# Power.net
KiCad netlist of a schematic drawn in Altium Designer
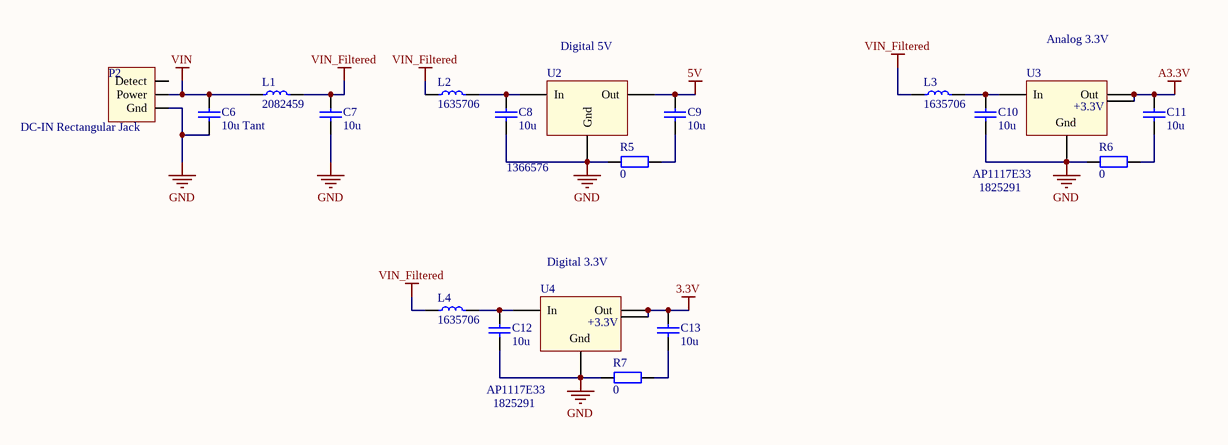
[diagram p0: Power.SchDoc]

(export (version "E")
  (design (tool "Eeschema 10.0.6"))
  (components
    (comp (ref "C6") (value "10u Tant") (footprint "CAPC3216M") (libsource (lib "Passives") (part "C")))
    (comp (ref "C7") (value "10u") (footprint "CAPC2012M") (libsource (lib "Passives") (part "C")))
    (comp (ref "C8") (value "10u") (footprint "CAPC2012M") (libsource (lib "Passives") (part "C")))
    (comp (ref "C9") (value "10u") (footprint "CAPC2012M") (libsource (lib "Passives") (part "C")))
    (comp (ref "C10") (value "10u") (footprint "CAPC2012M") (libsource (lib "Passives") (part "C")))
    (comp (ref "C11") (value "10u") (footprint "CAPC2012M") (libsource (lib "Passives") (part "C")))
    (comp (ref "C12") (value "10u") (footprint "CAPC2012M") (libsource (lib "Passives") (part "C")))
    (comp (ref "C13") (value "10u") (footprint "CAPC2012M") (libsource (lib "Passives") (part "C")))
    (comp (ref "L1")
      (value "Wurth_742792901")
      (footprint "WE_742792901")
      (description "Ferrite bead, 1.1k Ohm, 10A, (Wurth 742792901)")
      (fields (field (name "SUPPLIER PART NUMBER 1") "2082459"))
      (libsource (lib "Passives") (part "Wurth_742792901"))
    )
    (comp (ref "L2")
      (value "FerriteBead_600R")
      (footprint "INDC1608M")
      (description "Ferrite bead,  600 Ohm, 1A")
      (fields (field (name "SUPPLIER PART NUMBER 1") "1635706"))
      (libsource (lib "Passives") (part "FerriteBead_600R"))
    )
    (comp (ref "L3")
      (value "FerriteBead_600R")
      (footprint "INDC1608M")
      (description "Ferrite bead,  600 Ohm, 1A")
      (fields (field (name "SUPPLIER PART NUMBER 1") "1635706"))
      (libsource (lib "Passives") (part "FerriteBead_600R"))
    )
    (comp (ref "L4")
      (value "FerriteBead_600R")
      (footprint "INDC1608M")
      (description "Ferrite bead,  600 Ohm, 1A")
      (fields (field (name "SUPPLIER PART NUMBER 1") "1635706"))
      (libsource (lib "Passives") (part "FerriteBead_600R"))
    )
    (comp (ref "P2")
      (value "DC-IN Rectangular Jack")
      (footprint "DC-IN-RECT-JACK-PCB")
      (libsource (lib "Connectors") (part "DC-IN Rectangular Jack"))
    )
    (comp (ref "R5") (value "0") (footprint "RESC1608M") (libsource (lib "Passives") (part "R")))
    (comp (ref "R6") (value "0") (footprint "RESC1608M") (libsource (lib "Passives") (part "R")))
    (comp (ref "R7") (value "0") (footprint "RESC1608M") (libsource (lib "Passives") (part "R")))
    (comp (ref "U2")
      (value "L7805CD2T-TR")
      (footprint "D2PAK_M")
      (description "5V 500mA linear regulator, D2PAK-3")
      (fields (field (name "SUPPLIER PART NUMBER 1") "1366576"))
      (libsource (lib "Linear") (part "L7805CD2T-TR"))
    )
    (comp (ref "U3")
      (value "AP1117E33")
      (footprint "SOT223-4M")
      (description "3.3V 1A LDO linear regulator")
      (fields (field (name "SUPPLIER PART NUMBER 1") "1825291"))
      (libsource (lib "Linear") (part "AP1117E33"))
    )
    (comp (ref "U4")
      (value "AP1117E33")
      (footprint "SOT223-4M")
      (description "3.3V 1A LDO linear regulator")
      (fields (field (name "SUPPLIER PART NUMBER 1") "1825291"))
      (libsource (lib "Linear") (part "AP1117E33"))
    )
  )
  (nets
    (net (code "1") (name "3.3V") (class "Default")
      (node (ref "C13") (pin "2") (pinfunction "2_2") (pintype "passive"))
      (node (ref "U4") (pin "Out") (pinfunction "Out_Out") (pintype "power_in"))
      (node (ref "U4") (pin "Out2") (pinfunction "Out2_Out2") (pintype "power_in"))
    )
    (net (code "2") (name "5V") (class "Default")
      (node (ref "C9") (pin "2") (pinfunction "2_2") (pintype "passive"))
      (node (ref "U2") (pin "Out") (pinfunction "Out_Out") (pintype "power_in"))
    )
    (net (code "3") (name "A3.3V") (class "Default")
      (node (ref "C11") (pin "2") (pinfunction "2_2") (pintype "passive"))
      (node (ref "U3") (pin "Out") (pinfunction "Out_Out") (pintype "power_in"))
      (node (ref "U3") (pin "Out2") (pinfunction "Out2_Out2") (pintype "power_in"))
    )
    (net (code "4") (name "GND") (class "Default")
      (node (ref "C10") (pin "1") (pinfunction "1_1") (pintype "passive"))
      (node (ref "C12") (pin "1") (pinfunction "1_1") (pintype "passive"))
      (node (ref "C6") (pin "2") (pinfunction "2_2") (pintype "passive"))
      (node (ref "C7") (pin "1") (pinfunction "1_1") (pintype "passive"))
      (node (ref "C8") (pin "1") (pinfunction "1_1") (pintype "passive"))
      (node (ref "P2") (pin "Gnd") (pinfunction "Gnd_Gnd") (pintype "passive"))
      (node (ref "R5") (pin "2") (pinfunction "2_2") (pintype "passive"))
      (node (ref "R6") (pin "2") (pinfunction "2_2") (pintype "passive"))
      (node (ref "R7") (pin "2") (pinfunction "2_2") (pintype "passive"))
      (node (ref "U2") (pin "Gnd") (pinfunction "Gnd_Gnd") (pintype "passive"))
      (node (ref "U3") (pin "Gnd") (pinfunction "Gnd_Gnd") (pintype "passive"))
      (node (ref "U4") (pin "Gnd") (pinfunction "Gnd_Gnd") (pintype "passive"))
    )
    (net (code "5") (name "Net-(C8-Pad2)") (class "Default")
      (node (ref "C8") (pin "2") (pinfunction "2_2") (pintype "passive"))
      (node (ref "L2") (pin "2") (pinfunction "2_2") (pintype "passive"))
      (node (ref "U2") (pin "In") (pinfunction "In_In") (pintype "power_in"))
    )
    (net (code "6") (name "Net-(C9-Pad1)") (class "Default")
      (node (ref "C9") (pin "1") (pinfunction "1_1") (pintype "passive"))
      (node (ref "R5") (pin "1") (pinfunction "1_1") (pintype "passive"))
    )
    (net (code "7") (name "Net-(C10-Pad2)") (class "Default")
      (node (ref "C10") (pin "2") (pinfunction "2_2") (pintype "passive"))
      (node (ref "L3") (pin "2") (pinfunction "2_2") (pintype "passive"))
      (node (ref "U3") (pin "In") (pinfunction "In_In") (pintype "power_in"))
    )
    (net (code "8") (name "Net-(C11-Pad1)") (class "Default")
      (node (ref "C11") (pin "1") (pinfunction "1_1") (pintype "passive"))
      (node (ref "R6") (pin "1") (pinfunction "1_1") (pintype "passive"))
    )
    (net (code "9") (name "Net-(C12-Pad2)") (class "Default")
      (node (ref "C12") (pin "2") (pinfunction "2_2") (pintype "passive"))
      (node (ref "L4") (pin "2") (pinfunction "2_2") (pintype "passive"))
      (node (ref "U4") (pin "In") (pinfunction "In_In") (pintype "power_in"))
    )
    (net (code "10") (name "Net-(C13-Pad1)") (class "Default")
      (node (ref "C13") (pin "1") (pinfunction "1_1") (pintype "passive"))
      (node (ref "R7") (pin "1") (pinfunction "1_1") (pintype "passive"))
    )
    (net (code "11") (name "VIN") (class "Default")
      (node (ref "C6") (pin "1") (pinfunction "1_1") (pintype "passive"))
      (node (ref "L1") (pin "1") (pinfunction "1_1") (pintype "passive"))
      (node (ref "P2") (pin "Power") (pinfunction "Power_Power") (pintype "passive"))
    )
    (net (code "12") (name "VIN_Filtered") (class "Default")
      (node (ref "C7") (pin "2") (pinfunction "2_2") (pintype "passive"))
      (node (ref "L1") (pin "2") (pinfunction "2_2") (pintype "passive"))
      (node (ref "L2") (pin "1") (pinfunction "1_1") (pintype "passive"))
      (node (ref "L3") (pin "1") (pinfunction "1_1") (pintype "passive"))
      (node (ref "L4") (pin "1") (pinfunction "1_1") (pintype "passive"))
    )
    (net (code "13") (name "unconnected-(P2-PadDetect)") (class "Default")
      (node (ref "P2") (pin "Detect") (pinfunction "Detect_Detect") (pintype "passive"))
    )
  )
)
